# wifilamp3.net
KiCad netlist of a schematic drawn in EAGLE
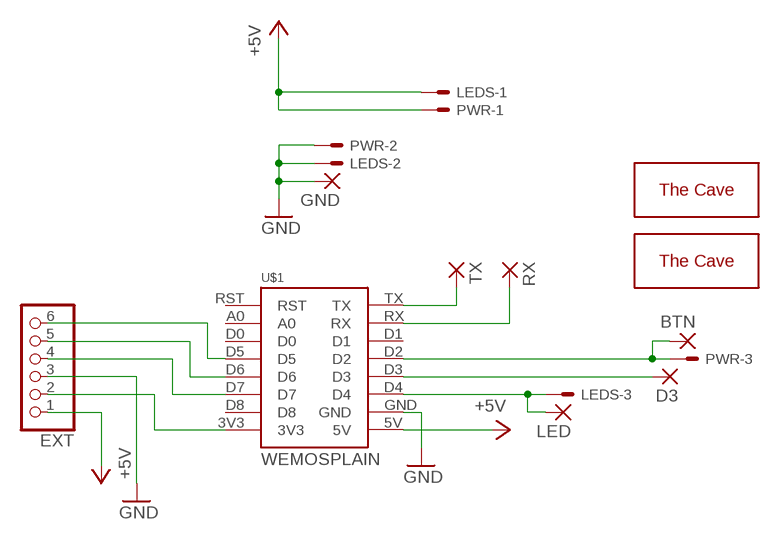
[diagram p0: schematic, sheet 1]

(export (version "E")
  (design (tool "Eeschema 10.0.6"))
  (components
    (comp (ref "BTN")
      (value "WIREPADSMD1,27-254")
      (footprint "eagle-import:SMD1,27-2,54")
      (libsource (lib "eagle-import") (part "WIREPADSMD1,27-254"))
    )
    (comp (ref "D3")
      (value "WIREPADSMD1,27-254")
      (footprint "eagle-import:SMD1,27-2,54")
      (libsource (lib "eagle-import") (part "WIREPADSMD1,27-254"))
    )
    (comp (ref "EXT")
      (value "PINHD-1X6")
      (footprint "eagle-import:1X06")
      (libsource (lib "eagle-import") (part "PINHD-1X6"))
    )
    (comp (ref "GND")
      (value "WIREPADSMD1,27-254")
      (footprint "eagle-import:SMD1,27-2,54")
      (libsource (lib "eagle-import") (part "WIREPADSMD1,27-254"))
    )
    (comp (ref "LED")
      (value "WIREPADSMD1,27-254")
      (footprint "eagle-import:SMD1,27-2,54")
      (libsource (lib "eagle-import") (part "WIREPADSMD1,27-254"))
    )
    (comp (ref "LEDS")
      (value "JST-XH-03-PIN-LONG-PAD")
      (footprint "eagle-import:JST-XH-03-PACKAGE-LONG-PAD")
      (libsource (lib "eagle-import") (part "JST-XH-03-PIN-LONG-PAD"))
    )
    (comp (ref "PWR")
      (value "JST-XH-03-PIN-LONG-PAD")
      (footprint "eagle-import:JST-XH-03-PACKAGE-LONG-PAD")
      (libsource (lib "eagle-import") (part "JST-XH-03-PIN-LONG-PAD"))
    )
    (comp (ref "RX")
      (value "WIREPADSMD1,27-254")
      (footprint "eagle-import:SMD1,27-2,54")
      (libsource (lib "eagle-import") (part "WIREPADSMD1,27-254"))
    )
    (comp (ref "TX")
      (value "WIREPADSMD1,27-254")
      (footprint "eagle-import:SMD1,27-2,54")
      (libsource (lib "eagle-import") (part "WIREPADSMD1,27-254"))
    )
    (comp (ref "U$1")
      (value "WEMOSPLAIN")
      (footprint "eagle-import:WEMOS-PLAIN")
      (libsource (lib "eagle-import") (part "WEMOSPLAIN"))
    )
    (comp (ref "U$2")
      (value "THECAVE_LOGO_TOP_MEDIUM")
      (footprint "eagle-import:LOGO_TOP_MED")
      (libsource (lib "eagle-import") (part "THECAVE_LOGO_TOP_MEDIUM"))
    )
    (comp (ref "U$3")
      (value "THECAVE_LOGO_BOTTOM_MEDIUM")
      (footprint "eagle-import:LOGO_BOT_MED")
      (libsource (lib "eagle-import") (part "THECAVE_LOGO_BOTTOM_MEDIUM"))
    )
  )
  (nets
    (net (code "1") (name "+5V") (class "Default")
      (node (ref "EXT") (pin "1") (pinfunction "1_1") (pintype "passive"))
      (node (ref "LEDS") (pin "1") (pinfunction "S_1") (pintype "passive"))
      (node (ref "PWR") (pin "1") (pinfunction "S_1") (pintype "passive"))
      (node (ref "U$1") (pin "5V") (pinfunction "5V_5V") (pintype "bidirectional"))
    )
    (net (code "2") (name "GND") (class "Default")
      (node (ref "EXT") (pin "3") (pinfunction "3_3") (pintype "passive"))
      (node (ref "GND") (pin "1") (pinfunction "P_1") (pintype "passive"))
      (node (ref "LEDS") (pin "2") (pinfunction "S_2") (pintype "passive"))
      (node (ref "PWR") (pin "2") (pinfunction "S_2") (pintype "passive"))
      (node (ref "U$1") (pin "GND") (pinfunction "GND_GND") (pintype "bidirectional"))
    )
    (net (code "3") (name "Net-(BTN-P)") (class "Default")
      (node (ref "BTN") (pin "1") (pinfunction "P_1") (pintype "passive"))
      (node (ref "PWR") (pin "3") (pinfunction "S_3") (pintype "passive"))
      (node (ref "U$1") (pin "D2") (pinfunction "D2_D2") (pintype "bidirectional"))
    )
    (net (code "4") (name "Net-(D3-P)") (class "Default")
      (node (ref "D3") (pin "1") (pinfunction "P_1") (pintype "passive"))
      (node (ref "U$1") (pin "D3") (pinfunction "D3_D3") (pintype "bidirectional"))
    )
    (net (code "5") (name "Net-(EXT-Pad2)") (class "Default")
      (node (ref "EXT") (pin "2") (pinfunction "2_2") (pintype "passive"))
      (node (ref "U$1") (pin "3V3") (pinfunction "3V3_3V3") (pintype "bidirectional"))
    )
    (net (code "6") (name "Net-(EXT-Pad4)") (class "Default")
      (node (ref "EXT") (pin "4") (pinfunction "4_4") (pintype "passive"))
      (node (ref "U$1") (pin "D7") (pinfunction "D7_D7") (pintype "bidirectional"))
    )
    (net (code "7") (name "Net-(EXT-Pad5)") (class "Default")
      (node (ref "EXT") (pin "5") (pinfunction "5_5") (pintype "passive"))
      (node (ref "U$1") (pin "D6") (pinfunction "D6_D6") (pintype "bidirectional"))
    )
    (net (code "8") (name "Net-(EXT-Pad6)") (class "Default")
      (node (ref "EXT") (pin "6") (pinfunction "6_6") (pintype "passive"))
      (node (ref "U$1") (pin "D5") (pinfunction "D5_D5") (pintype "bidirectional"))
    )
    (net (code "9") (name "Net-(LED-P)") (class "Default")
      (node (ref "LED") (pin "1") (pinfunction "P_1") (pintype "passive"))
      (node (ref "LEDS") (pin "3") (pinfunction "S_3") (pintype "passive"))
      (node (ref "U$1") (pin "D4") (pinfunction "D4_D4") (pintype "bidirectional"))
    )
    (net (code "10") (name "Net-(RX-P)") (class "Default")
      (node (ref "RX") (pin "1") (pinfunction "P_1") (pintype "passive"))
      (node (ref "U$1") (pin "RX") (pinfunction "RX_RX") (pintype "bidirectional"))
    )
    (net (code "11") (name "Net-(TX-P)") (class "Default")
      (node (ref "TX") (pin "1") (pinfunction "P_1") (pintype "passive"))
      (node (ref "U$1") (pin "TX") (pinfunction "TX_TX") (pintype "bidirectional"))
    )
    (net (code "12") (name "unconnected-(U$1-PadA0)") (class "Default")
      (node (ref "U$1") (pin "A0") (pinfunction "A0_A0") (pintype "bidirectional"))
    )
    (net (code "13") (name "unconnected-(U$1-PadD0)") (class "Default")
      (node (ref "U$1") (pin "D0") (pinfunction "D0_D0") (pintype "bidirectional"))
    )
    (net (code "14") (name "unconnected-(U$1-PadD1)") (class "Default")
      (node (ref "U$1") (pin "D1") (pinfunction "D1_D1") (pintype "bidirectional"))
    )
    (net (code "15") (name "unconnected-(U$1-PadD8)") (class "Default")
      (node (ref "U$1") (pin "D8") (pinfunction "D8_D8") (pintype "bidirectional"))
    )
    (net (code "16") (name "unconnected-(U$1-PadRST)") (class "Default")
      (node (ref "U$1") (pin "RST") (pinfunction "RST_RST") (pintype "bidirectional"))
    )
  )
)
